# SerialKM.net
KiCad netlist of a schematic drawn in Altium Designer
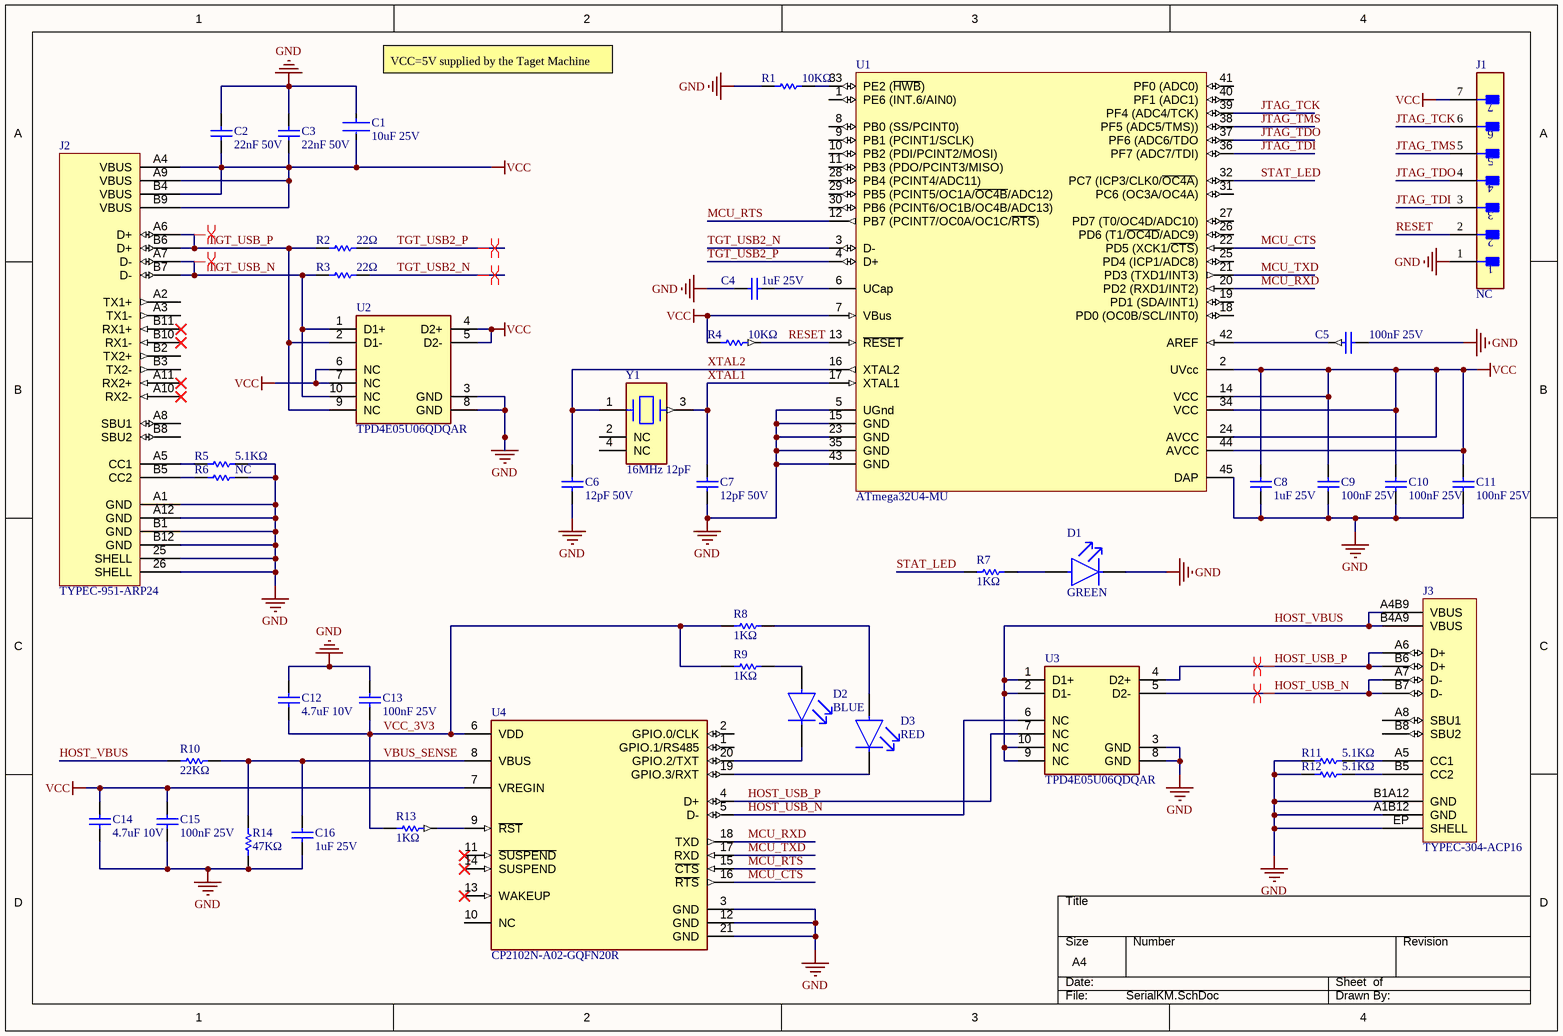
[diagram p0: SerialKM.SchDoc]

(export (version "E")
  (design (tool "Eeschema 10.0.6"))
  (components
    (comp (ref "C1")
      (value "10uF 25V")
      (footprint "FP-C1608-080-MFG")
      (description "CAP CER 10UF 25V X5R 0603")
      (fields (field (name "TOLERANCE") "20%"))
      (libsource (lib "Altium Content Vault") (part "11868f565c42a9108669ba33697ecf6"))
    )
    (comp (ref "C2")
      (value "22nF 50V")
      (footprint "CAPC1005X56X25LL10T15")
      (fields
        (field (name "PART NUMBER") "CM05X7R223K16AH.")
        (field (name "MANUFACTURER") "AVX Interconnect / Elco")
      )
      (libsource (lib "Altium Content Vault") (part "CAP"))
    )
    (comp (ref "C3")
      (value "22nF 50V")
      (footprint "CAPC1005X56X25LL10T15")
      (fields
        (field (name "PART NUMBER") "CM05X7R223K16AH.")
        (field (name "MANUFACTURER") "AVX Interconnect / Elco")
      )
      (libsource (lib "Altium Content Vault") (part "CAP"))
    )
    (comp (ref "C4")
      (value "1uF 25V")
      (footprint "CAPC1005X55X10LL05")
      (description "Chip Capacitor, 1 uF, +/- 10%, 16 V, -55 to 85 degC, 0402 (1005 Metric), RoHS, Tape and Reel")
      (fields
        (field (name "TOLERANCE") "±10%")
        (field (name "PCN PART NUMBER") "MLCCPartNumberChange30/Nov/2012")
      )
      (libsource (lib "Altium Content Vault") (part "CAP-NP-2"))
    )
    (comp (ref "C5")
      (value "100nF 25V")
      (footprint "CAPC1005X55X30LL05T10")
      (fields (field (name "MANUFACTURER") "Kemet") (field (name "PART NUMBER") "C0402C104K4RACTU"))
      (libsource (lib "") (part "CAP_1"))
    )
    (comp (ref "C6")
      (value "12pF 50V")
      (footprint "CAPC1005X61X26LL10T16")
      (fields (field (name "PART NUMBER") "VJ0402D120JXCAJ") (field (name "MANUFACTURER") "Vitramon"))
      (libsource (lib "Altium Content Vault") (part "CAP"))
    )
    (comp (ref "C7")
      (value "12pF 50V")
      (footprint "CAPC1005X61X26LL10T16")
      (fields (field (name "PART NUMBER") "VJ0402D120JXCAJ") (field (name "MANUFACTURER") "Vitramon"))
      (libsource (lib "Altium Content Vault") (part "CAP"))
    )
    (comp (ref "C8")
      (value "1uF 25V")
      (footprint "CAPC1005X55X10LL05")
      (description "Chip Capacitor, 1 uF, +/- 10%, 16 V, -55 to 85 degC, 0402 (1005 Metric), RoHS, Tape and Reel")
      (fields
        (field (name "TOLERANCE") "±10%")
        (field (name "PCN PART NUMBER") "MLCCPartNumberChange30/Nov/2012")
      )
      (libsource (lib "Altium Content Vault") (part "CAP-NP-2"))
    )
    (comp (ref "C9")
      (value "100nF 25V")
      (footprint "CAPC1005X55X30LL05T10")
      (fields (field (name "MANUFACTURER") "Kemet") (field (name "PART NUMBER") "C0402C104K4RACTU"))
      (libsource (lib "Altium Content Vault") (part "CAP"))
    )
    (comp (ref "C10")
      (value "100nF 25V")
      (footprint "CAPC1005X55X30LL05T10")
      (fields (field (name "MANUFACTURER") "Kemet") (field (name "PART NUMBER") "C0402C104K4RACTU"))
      (libsource (lib "Altium Content Vault") (part "CAP"))
    )
    (comp (ref "C11")
      (value "100nF 25V")
      (footprint "CAPC1005X55X30LL05T10")
      (fields (field (name "MANUFACTURER") "Kemet") (field (name "PART NUMBER") "C0402C104K4RACTU"))
      (libsource (lib "Altium Content Vault") (part "CAP"))
    )
    (comp (ref "C12")
      (value "4.7uF 10V")
      (footprint "CAPC1005X70X10LL20T00")
      (fields
        (field (name "MANUFACTURER") "AVX Interconnect / Elco")
        (field (name "PART NUMBER") "TACK475M003QTA")
      )
      (libsource (lib "Altium Content Vault") (part "CAP"))
    )
    (comp (ref "C13")
      (value "100nF 25V")
      (footprint "CAPC1005X55X30LL05T10")
      (fields (field (name "MANUFACTURER") "Kemet") (field (name "PART NUMBER") "C0402C104K4RACTU"))
      (libsource (lib "Altium Content Vault") (part "CAP"))
    )
    (comp (ref "C14")
      (value "4.7uF 10V")
      (footprint "CAPC1005X70X10LL20T00")
      (fields
        (field (name "MANUFACTURER") "AVX Interconnect / Elco")
        (field (name "PART NUMBER") "TACK475M003QTA")
      )
      (libsource (lib "Altium Content Vault") (part "CAP"))
    )
    (comp (ref "C15")
      (value "100nF 25V")
      (footprint "CAPC1005X55X30LL05T10")
      (fields (field (name "MANUFACTURER") "Kemet") (field (name "PART NUMBER") "C0402C104K4RACTU"))
      (libsource (lib "Altium Content Vault") (part "CAP"))
    )
    (comp (ref "C16")
      (value "1uF 25V")
      (footprint "CAPC1005X55X10LL05")
      (description "Chip Capacitor, 1 uF, +/- 10%, 16 V, -55 to 85 degC, 0402 (1005 Metric), RoHS, Tape and Reel")
      (fields
        (field (name "TOLERANCE") "±10%")
        (field (name "PCN PART NUMBER") "MLCCPartNumberChange30/Nov/2012")
      )
      (libsource (lib "Altium Content Vault") (part "CAP-NP-2"))
    )
    (comp (ref "D1")
      (value "GREEN")
      (footprint "FP-APHHS1005CGCK-MFG")
      (description "LED CLEAR CHIP SMD")
      (libsource (lib "Altium Content Vault") (part "8706943c75ba83719d021d2fdc84c58"))
    )
    (comp (ref "D2")
      (value "BLUE")
      (footprint "FP-APHHS1005CGCK-MFG")
      (description "LED CLEAR CHIP SMD")
      (libsource (lib "Altium Content Vault") (part "8706943c75ba83719d021d2fdc84c58"))
    )
    (comp (ref "D3")
      (value "RED")
      (footprint "FP-APHHS1005CGCK-MFG")
      (description "LED CLEAR CHIP SMD")
      (libsource (lib "Altium Content Vault") (part "8706943c75ba83719d021d2fdc84c58"))
    )
    (comp (ref "J1")
      (value "NC")
      (footprint "FP-GRPB071VWVN-RC-MFG")
      (description "Debug header")
      (libsource (lib "Altium Content Vault") (part "5bcee6b94e1fee4be3f4cc3a650a442"))
    )
    (comp (ref "J2")
      (value "TYPEC-951-ARP24")
      (footprint "TYPEC-951-ARP24")
      (description "Xunpu TYPEC-951-ARP24 USB Type-C Male Connector SMD")
      (libsource (lib "SerialKM") (part "TYPEC-951-ARP24"))
    )
    (comp (ref "J3")
      (value "TYPEC-304-ACP16")
      (footprint "TYPEC-304-ACP16")
      (description "Xunpu TYPEC-304-ACP16 USB Type-C  Socket 16P SMD")
      (libsource (lib "SerialKM") (part "TYPEC-304-ACP16"))
    )
    (comp (ref "R1")
      (value "10KΩ")
      (footprint "RESC1005X40X25LL05T10")
      (fields (field (name "PART NUMBER") "RC0402FR-075K1L") (field (name "MANUFACTURER") "Yageo / Phycomp"))
      (libsource (lib "Altium Content Vault") (part "RES"))
    )
    (comp (ref "R2")
      (value "22Ω")
      (footprint "RESC1005X40X25LL05T05")
      (fields (field (name "MANUFACTURER") "Vishay Dale") (field (name "PART NUMBER") "CRCW040222R0FKED"))
      (libsource (lib "Altium Content Vault") (part "RES"))
    )
    (comp (ref "R3")
      (value "22Ω")
      (footprint "RESC1005X40X25LL05T05")
      (fields (field (name "MANUFACTURER") "Vishay Dale") (field (name "PART NUMBER") "CRCW040222R0FKED"))
      (libsource (lib "Altium Content Vault") (part "RES"))
    )
    (comp (ref "R4")
      (value "10KΩ")
      (footprint "RESC1005X40X25LL05T10")
      (fields (field (name "PART NUMBER") "RC0402FR-075K1L") (field (name "MANUFACTURER") "Yageo / Phycomp"))
      (libsource (lib "") (part "RES_2"))
    )
    (comp (ref "R5")
      (value "5.1KΩ")
      (footprint "RESC1005X40X25LL05T10")
      (fields (field (name "PART NUMBER") "RC0402FR-075K1L") (field (name "MANUFACTURER") "Yageo / Phycomp"))
      (libsource (lib "Altium Content Vault") (part "RES"))
    )
    (comp (ref "R6")
      (value "NC")
      (footprint "RESC1005X40X25LL05T10")
      (fields (field (name "PART NUMBER") "RC0402FR-075K1L") (field (name "MANUFACTURER") "Yageo / Phycomp"))
      (libsource (lib "Altium Content Vault") (part "RES"))
    )
    (comp (ref "R7")
      (value "1KΩ")
      (footprint "RESC1005X40X25LL05T10")
      (fields (field (name "PART NUMBER") "RC0402FR-075K1L") (field (name "MANUFACTURER") "Yageo / Phycomp"))
      (libsource (lib "Altium Content Vault") (part "RES"))
    )
    (comp (ref "R8")
      (value "1KΩ")
      (footprint "RESC1005X40X25LL05T10")
      (fields (field (name "PART NUMBER") "RC0402FR-075K1L") (field (name "MANUFACTURER") "Yageo / Phycomp"))
      (libsource (lib "Altium Content Vault") (part "RES"))
    )
    (comp (ref "R9")
      (value "1KΩ")
      (footprint "RESC1005X40X25LL05T10")
      (fields (field (name "PART NUMBER") "RC0402FR-075K1L") (field (name "MANUFACTURER") "Yageo / Phycomp"))
      (libsource (lib "Altium Content Vault") (part "RES"))
    )
    (comp (ref "R10")
      (value "22KΩ")
      (footprint "RESC1005X40X25LL05T10")
      (fields (field (name "PART NUMBER") "RC0402FR-075K1L") (field (name "MANUFACTURER") "Yageo / Phycomp"))
      (libsource (lib "Altium Content Vault") (part "RES"))
    )
    (comp (ref "R11")
      (value "5.1KΩ")
      (footprint "RESC1005X40X25LL05T10")
      (fields (field (name "PART NUMBER") "RC0402FR-075K1L") (field (name "MANUFACTURER") "Yageo / Phycomp"))
      (libsource (lib "Altium Content Vault") (part "RES"))
    )
    (comp (ref "R12")
      (value "5.1KΩ")
      (footprint "RESC1005X40X25LL05T10")
      (fields (field (name "PART NUMBER") "RC0402FR-075K1L") (field (name "MANUFACTURER") "Yageo / Phycomp"))
      (libsource (lib "Altium Content Vault") (part "RES"))
    )
    (comp (ref "R13")
      (value "1KΩ")
      (footprint "RESC1005X40X25LL05T10")
      (fields (field (name "PART NUMBER") "RC0402FR-075K1L") (field (name "MANUFACTURER") "Yageo / Phycomp"))
      (libsource (lib "") (part "RES_1"))
    )
    (comp (ref "R14")
      (value "47KΩ")
      (footprint "RESC1005X40X25LL05T10")
      (fields (field (name "PART NUMBER") "RC0402FR-075K1L") (field (name "MANUFACTURER") "Yageo / Phycomp"))
      (libsource (lib "Altium Content Vault") (part "RES"))
    )
    (comp (ref "U1")
      (value "ATmega32U4-MU")
      (footprint "44PW_L")
      (libsource (lib "Altium Content Vault") (part "MC-8B-ATM16U4-SQ45"))
    )
    (comp (ref "U2")
      (value "TPD4E05U06QDQAR")
      (footprint "FP-DQA0010A-MFG")
      (description "TVS DIODE 5.5V 14V 10USON")
      (fields
        (field (name "MANUFACTURER PART NUMBER") "TPD4E05U06QDQARQ1")
        (field (name "OCTOPART") "https://octopart.com/tpd4e05u06qdqarq1-texas+instruments-48523459")
      )
      (libsource (lib "Altium Content Vault") (part "f11f7ff102fa2b028e1355c732c836d"))
    )
    (comp (ref "U3")
      (value "TPD4E05U06QDQAR")
      (footprint "FP-DQA0010A-MFG")
      (description "TVS DIODE 5.5V 14V 10USON")
      (fields
        (field (name "MANUFACTURER PART NUMBER") "TPD4E05U06QDQARQ1")
        (field (name "OCTOPART") "https://octopart.com/tpd4e05u06qdqarq1-texas+instruments-48523459")
      )
      (libsource (lib "Altium Content Vault") (part "f11f7ff102fa2b028e1355c732c836d"))
    )
    (comp (ref "U4")
      (value "CP2102N-A02-GQFN20R")
      (footprint "FP-CP2102N-A02-GQFN20R-MFG")
      (description "IC USB TO UART BRIDGE QFN20")
      (libsource (lib "Altium Content Vault") (part "12297b18919ed2bc2a0fed00377f037"))
    )
    (comp (ref "Y1")
      (value "16MHz 12pF")
      (footprint "FP-XRCGB-MFG")
      (description "CRYSTAL 16.0000MHZ")
      (fields (field (name "TOLERANCE") "20ppm"))
      (libsource (lib "Altium Content Vault") (part "069643b213014e47d16623c4b5cd2db"))
    )
  )
  (nets
    (net (code "1") (name "/HOST_USB_N") (class "Default")
      (node (ref "J3") (pin "A7") (pinfunction "D-_A7") (pintype "bidirectional"))
      (node (ref "J3") (pin "B7") (pinfunction "D-_B7") (pintype "bidirectional"))
      (node (ref "U3") (pin "5") (pinfunction "D2-_5") (pintype "passive"))
      (node (ref "U3") (pin "6") (pinfunction "NC_6") (pintype "passive"))
      (node (ref "U4") (pin "5") (pinfunction "D-_5") (pintype "bidirectional"))
    )
    (net (code "2") (name "/HOST_USB_P") (class "Default")
      (node (ref "J3") (pin "A6") (pinfunction "D+_A6") (pintype "bidirectional"))
      (node (ref "J3") (pin "B6") (pinfunction "D+_B6") (pintype "bidirectional"))
      (node (ref "U3") (pin "4") (pinfunction "D2+_4") (pintype "passive"))
      (node (ref "U3") (pin "7") (pinfunction "NC_7") (pintype "passive"))
      (node (ref "U4") (pin "4") (pinfunction "D+_4") (pintype "bidirectional"))
    )
    (net (code "3") (name "/HOST_VBUS") (class "Default")
      (node (ref "J3") (pin "A4B9") (pinfunction "VBUS_A4B9") (pintype "passive"))
      (node (ref "J3") (pin "B4A9") (pinfunction "VBUS_B4A9") (pintype "passive"))
      (node (ref "R10") (pin "1") (pinfunction "1_1") (pintype "passive"))
      (node (ref "U3") (pin "1") (pinfunction "D1+_1") (pintype "passive"))
      (node (ref "U3") (pin "10") (pinfunction "NC_10") (pintype "passive"))
      (node (ref "U3") (pin "2") (pinfunction "D1-_2") (pintype "passive"))
      (node (ref "U3") (pin "9") (pinfunction "NC_9") (pintype "passive"))
    )
    (net (code "4") (name "/JTAG_TCK") (class "Default")
      (node (ref "J1") (pin "6") (pinfunction "6_6") (pintype "passive"))
      (node (ref "U1") (pin "39") (pinfunction "PF4_(ADC4/TCK)_39") (pintype "bidirectional"))
    )
    (net (code "5") (name "/JTAG_TDI") (class "Default")
      (node (ref "J1") (pin "3") (pinfunction "3_3") (pintype "passive"))
      (node (ref "U1") (pin "36") (pinfunction "PF7_(ADC7/TDI)_36") (pintype "bidirectional"))
    )
    (net (code "6") (name "/JTAG_TDO") (class "Default")
      (node (ref "J1") (pin "4") (pinfunction "4_4") (pintype "passive"))
      (node (ref "U1") (pin "37") (pinfunction "PF6_(ADC6/TDO_37") (pintype "bidirectional"))
    )
    (net (code "7") (name "/JTAG_TMS") (class "Default")
      (node (ref "J1") (pin "5") (pinfunction "5_5") (pintype "passive"))
      (node (ref "U1") (pin "38") (pinfunction "PF5_(ADC5/TMS))_38") (pintype "bidirectional"))
    )
    (net (code "8") (name "/MCU_CTS") (class "Default")
      (node (ref "U1") (pin "22") (pinfunction "PD5_(XCK1/~{CTS})_22") (pintype "input"))
      (node (ref "U4") (pin "16") (pinfunction "~{RTS}_16") (pintype "output"))
    )
    (net (code "9") (name "/MCU_RTS") (class "Default")
      (node (ref "U1") (pin "12") (pinfunction "PB7_(PCINT7/OC0A/OC1C/~{RTS})_12") (pintype "output"))
      (node (ref "U4") (pin "15") (pinfunction "~{CTS}_15") (pintype "input"))
    )
    (net (code "10") (name "/MCU_RXD") (class "Default")
      (node (ref "U1") (pin "20") (pinfunction "PD2_(RXD1/INT2)_20") (pintype "input"))
      (node (ref "U4") (pin "18") (pinfunction "TXD_18") (pintype "output"))
    )
    (net (code "11") (name "/MCU_TXD") (class "Default")
      (node (ref "U1") (pin "21") (pinfunction "PD3_(TXD1/INT3)_21") (pintype "output"))
      (node (ref "U4") (pin "17") (pinfunction "RXD_17") (pintype "input"))
    )
    (net (code "12") (name "/RESET") (class "Default")
      (node (ref "J1") (pin "2") (pinfunction "2_2") (pintype "passive"))
      (node (ref "R4") (pin "1") (pinfunction "1_1") (pintype "output"))
      (node (ref "U1") (pin "13") (pinfunction "~{RESET}_13") (pintype "input"))
    )
    (net (code "13") (name "/STAT_LED") (class "Default")
      (node (ref "R7") (pin "1") (pinfunction "1_1") (pintype "passive"))
      (node (ref "U1") (pin "32") (pinfunction "PC7_(ICP3/CLK0/~{OC4A})_32") (pintype "bidirectional"))
    )
    (net (code "14") (name "/TGT_USB2_N") (class "Default")
      (node (ref "R3") (pin "2") (pinfunction "2_2") (pintype "passive"))
      (node (ref "U1") (pin "3") (pinfunction "D-_3") (pintype "bidirectional"))
    )
    (net (code "15") (name "/TGT_USB2_P") (class "Default")
      (node (ref "R2") (pin "2") (pinfunction "2_2") (pintype "passive"))
      (node (ref "U1") (pin "4") (pinfunction "D+_4") (pintype "bidirectional"))
    )
    (net (code "16") (name "/TGT_USB_N") (class "Default")
      (node (ref "J2") (pin "A7") (pinfunction "D-_A7") (pintype "bidirectional"))
      (node (ref "J2") (pin "B7") (pinfunction "D-_B7") (pintype "bidirectional"))
      (node (ref "R3") (pin "1") (pinfunction "1_1") (pintype "passive"))
      (node (ref "U2") (pin "1") (pinfunction "D1+_1") (pintype "passive"))
      (node (ref "U2") (pin "10") (pinfunction "NC_10") (pintype "passive"))
    )
    (net (code "17") (name "/TGT_USB_P") (class "Default")
      (node (ref "J2") (pin "A6") (pinfunction "D+_A6") (pintype "bidirectional"))
      (node (ref "J2") (pin "B6") (pinfunction "D+_B6") (pintype "bidirectional"))
      (node (ref "R2") (pin "1") (pinfunction "1_1") (pintype "passive"))
      (node (ref "U2") (pin "2") (pinfunction "D1-_2") (pintype "passive"))
      (node (ref "U2") (pin "9") (pinfunction "NC_9") (pintype "passive"))
    )
    (net (code "18") (name "/VBUS_SENSE") (class "Default")
      (node (ref "C16") (pin "2") (pinfunction "2_2") (pintype "passive"))
      (node (ref "R10") (pin "2") (pinfunction "2_2") (pintype "passive"))
      (node (ref "R14") (pin "2") (pinfunction "2_2") (pintype "passive"))
      (node (ref "U4") (pin "8") (pinfunction "VBUS_8") (pintype "power_in"))
    )
    (net (code "19") (name "/VCC_3V3") (class "Default")
      (node (ref "C12") (pin "1") (pinfunction "1_1") (pintype "passive"))
      (node (ref "C13") (pin "1") (pinfunction "1_1") (pintype "passive"))
      (node (ref "R13") (pin "1") (pinfunction "1_1") (pintype "passive"))
      (node (ref "R8") (pin "1") (pinfunction "1_1") (pintype "passive"))
      (node (ref "R9") (pin "2") (pinfunction "2_2") (pintype "passive"))
      (node (ref "U4") (pin "6") (pinfunction "VDD_6") (pintype "power_in"))
    )
    (net (code "20") (name "/XTAL1") (class "Default")
      (node (ref "C7") (pin "2") (pinfunction "2_2") (pintype "passive"))
      (node (ref "U1") (pin "17") (pinfunction "XTAL1_17") (pintype "input"))
      (node (ref "Y1") (pin "3") (pinfunction "2_Crystal_terminal_3") (pintype "output"))
    )
    (net (code "21") (name "/XTAL2") (class "Default")
      (node (ref "C6") (pin "2") (pinfunction "2_2") (pintype "passive"))
      (node (ref "U1") (pin "16") (pinfunction "XTAL2_16") (pintype "output"))
      (node (ref "Y1") (pin "1") (pinfunction "1_Crystal_terminal_1") (pintype "passive"))
    )
    (net (code "22") (name "GND") (class "Default")
      (node (ref "C1") (pin "1") (pinfunction "1_1") (pintype "passive"))
      (node (ref "C10") (pin "1") (pinfunction "1_1") (pintype "passive"))
      (node (ref "C11") (pin "1") (pinfunction "1_1") (pintype "passive"))
      (node (ref "C12") (pin "2") (pinfunction "2_2") (pintype "passive"))
      (node (ref "C13") (pin "2") (pinfunction "2_2") (pintype "passive"))
      (node (ref "C14") (pin "1") (pinfunction "1_1") (pintype "passive"))
      (node (ref "C15") (pin "1") (pinfunction "1_1") (pintype "passive"))
      (node (ref "C16") (pin "1") (pinfunction "1_1") (pintype "passive"))
      (node (ref "C2") (pin "2") (pinfunction "2_2") (pintype "passive"))
      (node (ref "C3") (pin "2") (pinfunction "2_2") (pintype "passive"))
      (node (ref "C4") (pin "1") (pinfunction "1_1") (pintype "passive"))
      (node (ref "C5") (pin "1") (pinfunction "1_1") (pintype "passive"))
      (node (ref "C6") (pin "1") (pinfunction "1_1") (pintype "passive"))
      (node (ref "C7") (pin "1") (pinfunction "1_1") (pintype "passive"))
      (node (ref "C8") (pin "2") (pinfunction "2_2") (pintype "passive"))
      (node (ref "C9") (pin "1") (pinfunction "1_1") (pintype "passive"))
      (node (ref "D1") (pin "1") (pinfunction "C_1") (pintype "passive"))
      (node (ref "J1") (pin "1") (pinfunction "1_1") (pintype "passive"))
      (node (ref "J2") (pin "25") (pinfunction "SHELL_25") (pintype "passive"))
      (node (ref "J2") (pin "26") (pinfunction "SHELL_26") (pintype "passive"))
      (node (ref "J2") (pin "A1") (pinfunction "GND_A1") (pintype "passive"))
      (node (ref "J2") (pin "A12") (pinfunction "GND_A12") (pintype "passive"))
      (node (ref "J2") (pin "B1") (pinfunction "GND_B1") (pintype "passive"))
      (node (ref "J2") (pin "B12") (pinfunction "GND_B12") (pintype "passive"))
      (node (ref "J3") (pin "A1B12") (pinfunction "GND_A1B12") (pintype "passive"))
      (node (ref "J3") (pin "B1A12") (pinfunction "GND_B1A12") (pintype "passive"))
      (node (ref "J3") (pin "EP") (pinfunction "SHELL_EP") (pintype "passive"))
      (node (ref "R1") (pin "2") (pinfunction "2_2") (pintype "passive"))
      (node (ref "R11") (pin "1") (pinfunction "1_1") (pintype "passive"))
      (node (ref "R12") (pin "1") (pinfunction "1_1") (pintype "passive"))
      (node (ref "R14") (pin "1") (pinfunction "1_1") (pintype "passive"))
      (node (ref "R5") (pin "2") (pinfunction "2_2") (pintype "passive"))
      (node (ref "R6") (pin "2") (pinfunction "2_2") (pintype "passive"))
      (node (ref "U1") (pin "15") (pinfunction "GND_15") (pintype "power_in"))
      (node (ref "U1") (pin "23") (pinfunction "GND_23") (pintype "power_in"))
      (node (ref "U1") (pin "35") (pinfunction "GND_35") (pintype "power_in"))
      (node (ref "U1") (pin "43") (pinfunction "GND_43") (pintype "power_in"))
      (node (ref "U1") (pin "45") (pinfunction "DAP_45") (pintype "power_in"))
      (node (ref "U1") (pin "5") (pinfunction "UGnd_5") (pintype "power_in"))
      (node (ref "U2") (pin "3") (pinfunction "GND_3") (pintype "power_in"))
      (node (ref "U2") (pin "8") (pinfunction "GND_8") (pintype "power_in"))
      (node (ref "U3") (pin "3") (pinfunction "GND_3") (pintype "power_in"))
      (node (ref "U3") (pin "8") (pinfunction "GND_8") (pintype "power_in"))
      (node (ref "U4") (pin "12") (pinfunction "GND_12") (pintype "power_in"))
      (node (ref "U4") (pin "21") (pinfunction "GND_21") (pintype "power_in"))
      (node (ref "U4") (pin "3") (pinfunction "GND_3") (pintype "power_in"))
    )
    (net (code "23") (name "Net-(D1-A)") (class "Default")
      (node (ref "D1") (pin "2") (pinfunction "A_2") (pintype "passive"))
      (node (ref "R7") (pin "2") (pinfunction "2_2") (pintype "passive"))
    )
    (net (code "24") (name "Net-(D2-A)") (class "Default")
      (node (ref "D2") (pin "2") (pinfunction "A_2") (pintype "passive"))
      (node (ref "R9") (pin "1") (pinfunction "1_1") (pintype "passive"))
    )
    (net (code "25") (name "Net-(D2-C)") (class "Default")
      (node (ref "D2") (pin "1") (pinfunction "C_1") (pintype "passive"))
      (node (ref "U4") (pin "20") (pinfunction "GPIO.2/TXT_20") (pintype "bidirectional"))
    )
    (net (code "26") (name "Net-(D3-A)") (class "Default")
      (node (ref "D3") (pin "2") (pinfunction "A_2") (pintype "passive"))
      (node (ref "R8") (pin "2") (pinfunction "2_2") (pintype "passive"))
    )
    (net (code "27") (name "Net-(D3-C)") (class "Default")
      (node (ref "D3") (pin "1") (pinfunction "C_1") (pintype "passive"))
      (node (ref "U4") (pin "19") (pinfunction "GPIO.3/RXT_19") (pintype "bidirectional"))
    )
    (net (code "28") (name "Net-(J2-CC1)") (class "Default")
      (node (ref "J2") (pin "A5") (pinfunction "CC1_A5") (pintype "passive"))
      (node (ref "R5") (pin "1") (pinfunction "1_1") (pintype "passive"))
    )
    (net (code "29") (name "Net-(J2-CC2)") (class "Default")
      (node (ref "J2") (pin "B5") (pinfunction "CC2_B5") (pintype "passive"))
      (node (ref "R6") (pin "1") (pinfunction "1_1") (pintype "passive"))
    )
    (net (code "30") (name "Net-(J3-CC1)") (class "Default")
      (node (ref "J3") (pin "A5") (pinfunction "CC1_A5") (pintype "passive"))
      (node (ref "R11") (pin "2") (pinfunction "2_2") (pintype "passive"))
    )
    (net (code "31") (name "Net-(J3-CC2)") (class "Default")
      (node (ref "J3") (pin "B5") (pinfunction "CC2_B5") (pintype "passive"))
      (node (ref "R12") (pin "2") (pinfunction "2_2") (pintype "passive"))
    )
    (net (code "32") (name "Net-(U1-AREF)") (class "Default")
      (node (ref "C5") (pin "2") (pinfunction "2_2") (pintype "output"))
      (node (ref "U1") (pin "42") (pinfunction "AREF_42") (pintype "input"))
    )
    (net (code "33") (name "Net-(U1-PE2_(~{HWB}))") (class "Default")
      (node (ref "R1") (pin "1") (pinfunction "1_1") (pintype "passive"))
      (node (ref "U1") (pin "33") (pinfunction "PE2_(~{HWB})_33") (pintype "bidirectional"))
    )
    (net (code "34") (name "Net-(U1-UCap)") (class "Default")
      (node (ref "C4") (pin "2") (pinfunction "2_2") (pintype "passive"))
      (node (ref "U1") (pin "6") (pinfunction "UCap_6") (pintype "passive"))
    )
    (net (code "35") (name "Net-(U4-~{RST})") (class "Default")
      (node (ref "R13") (pin "2") (pinfunction "2_2") (pintype "output"))
      (node (ref "U4") (pin "9") (pinfunction "~{RST}_9") (pintype "input"))
    )
    (net (code "36") (name "VCC") (class "Default")
      (node (ref "C1") (pin "2") (pinfunction "2_2") (pintype "passive"))
      (node (ref "C10") (pin "2") (pinfunction "2_2") (pintype "passive"))
      (node (ref "C11") (pin "2") (pinfunction "2_2") (pintype "passive"))
      (node (ref "C14") (pin "2") (pinfunction "2_2") (pintype "passive"))
      (node (ref "C15") (pin "2") (pinfunction "2_2") (pintype "passive"))
      (node (ref "C2") (pin "1") (pinfunction "1_1") (pintype "passive"))
      (node (ref "C3") (pin "1") (pinfunction "1_1") (pintype "passive"))
      (node (ref "C8") (pin "1") (pinfunction "1_1") (pintype "passive"))
      (node (ref "C9") (pin "2") (pinfunction "2_2") (pintype "passive"))
      (node (ref "J1") (pin "7") (pinfunction "7_7") (pintype "passive"))
      (node (ref "J2") (pin "A4") (pinfunction "VBUS_A4") (pintype "power_in"))
      (node (ref "J2") (pin "A9") (pinfunction "VBUS_A9") (pintype "power_in"))
      (node (ref "J2") (pin "B4") (pinfunction "VBUS_B4") (pintype "power_in"))
      (node (ref "J2") (pin "B9") (pinfunction "VBUS_B9") (pintype "power_in"))
      (node (ref "R4") (pin "2") (pinfunction "2_2") (pintype "passive"))
      (node (ref "U1") (pin "14") (pinfunction "VCC_14") (pintype "power_in"))
      (node (ref "U1") (pin "2") (pinfunction "UVcc_2") (pintype "power_in"))
      (node (ref "U1") (pin "24") (pinfunction "AVCC_24") (pintype "power_in"))
      (node (ref "U1") (pin "34") (pinfunction "VCC_34") (pintype "power_in"))
      (node (ref "U1") (pin "44") (pinfunction "AVCC_44") (pintype "power_in"))
      (node (ref "U1") (pin "7") (pinfunction "VBus_7") (pintype "input"))
      (node (ref "U2") (pin "4") (pinfunction "D2+_4") (pintype "passive"))
      (node (ref "U2") (pin "5") (pinfunction "D2-_5") (pintype "passive"))
      (node (ref "U2") (pin "6") (pinfunction "NC_6") (pintype "passive"))
      (node (ref "U2") (pin "7") (pinfunction "NC_7") (pintype "passive"))
      (node (ref "U4") (pin "7") (pinfunction "VREGIN_7") (pintype "passive"))
    )
    (net (code "37") (name "unconnected-(J2-RX1+-PadB11)") (class "Default")
      (node (ref "J2") (pin "B11") (pinfunction "RX1+_B11") (pintype "input+no_connect"))
    )
    (net (code "38") (name "unconnected-(J2-RX1--PadB10)") (class "Default")
      (node (ref "J2") (pin "B10") (pinfunction "RX1-_B10") (pintype "input+no_connect"))
    )
    (net (code "39") (name "unconnected-(J2-RX2+-PadA11)") (class "Default")
      (node (ref "J2") (pin "A11") (pinfunction "RX2+_A11") (pintype "input+no_connect"))
    )
    (net (code "40") (name "unconnected-(J2-RX2--PadA10)") (class "Default")
      (node (ref "J2") (pin "A10") (pinfunction "RX2-_A10") (pintype "input+no_connect"))
    )
    (net (code "41") (name "unconnected-(J2-SBU1-PadA8)") (class "Default")
      (node (ref "J2") (pin "A8") (pinfunction "SBU1_A8") (pintype "bidirectional"))
    )
    (net (code "42") (name "unconnected-(J2-SBU2-PadB8)") (class "Default")
      (node (ref "J2") (pin "B8") (pinfunction "SBU2_B8") (pintype "bidirectional"))
    )
    (net (code "43") (name "unconnected-(J2-TX1+-PadA2)") (class "Default")
      (node (ref "J2") (pin "A2") (pinfunction "TX1+_A2") (pintype "output"))
    )
    (net (code "44") (name "unconnected-(J2-TX1--PadA3)") (class "Default")
      (node (ref "J2") (pin "A3") (pinfunction "TX1-_A3") (pintype "output"))
    )
    (net (code "45") (name "unconnected-(J2-TX2+-PadB2)") (class "Default")
      (node (ref "J2") (pin "B2") (pinfunction "TX2+_B2") (pintype "output"))
    )
    (net (code "46") (name "unconnected-(J2-TX2--PadB3)") (class "Default")
      (node (ref "J2") (pin "B3") (pinfunction "TX2-_B3") (pintype "output"))
    )
    (net (code "47") (name "unconnected-(J3-SBU1-PadA8)") (class "Default")
      (node (ref "J3") (pin "A8") (pinfunction "SBU1_A8") (pintype "bidirectional"))
    )
    (net (code "48") (name "unconnected-(J3-SBU2-PadB8)") (class "Default")
      (node (ref "J3") (pin "B8") (pinfunction "SBU2_B8") (pintype "bidirectional"))
    )
    (net (code "49") (name "unconnected-(U1-PB0_(SS{slash}PCINT0)-Pad8)") (class "Default")
      (node (ref "U1") (pin "8") (pinfunction "PB0_(SS/PCINT0)_8") (pintype "bidirectional"))
    )
    (net (code "50") (name "unconnected-(U1-PB1_(PCINT1{slash}SCLK)-Pad9)") (class "Default")
      (node (ref "U1") (pin "9") (pinfunction "PB1_(PCINT1/SCLK)_9") (pintype "bidirectional"))
    )
    (net (code "51") (name "unconnected-(U1-PB2_(PDI{slash}PCINT2{slash}MOSI)-Pad10)") (class "Default")
      (node (ref "U1") (pin "10") (pinfunction "PB2_(PDI/PCINT2/MOSI)_10") (pintype "bidirectional"))
    )
    (net (code "52") (name "unconnected-(U1-PB3_(PDO{slash}PCINT3{slash}MISO)-Pad11)") (class "Default")
      (node (ref "U1") (pin "11") (pinfunction "PB3_(PDO/PCINT3/MISO)_11") (pintype "bidirectional"))
    )
    (net (code "53") (name "unconnected-(U1-PB4_(PCINT4{slash}ADC11)-Pad28)") (class "Default")
      (node (ref "U1") (pin "28") (pinfunction "PB4_(PCINT4/ADC11)_28") (pintype "bidirectional"))
    )
    (net (code "54") (name "unconnected-(U1-PB5_(PCINT5{slash}OC1A{slash}~{OC4B}{slash}ADC12)-Pad29)") (class "Default")
      (node (ref "U1") (pin "29") (pinfunction "PB5_(PCINT5/OC1A/~{OC4B}/ADC12)_29") (pintype "bidirectional"))
    )
    (net (code "55") (name "unconnected-(U1-PB6_(PCINT6{slash}OC1B{slash}OC4B{slash}ADC13)-Pad30)") (class "Default")
      (node (ref "U1") (pin "30") (pinfunction "PB6_(PCINT6/OC1B/OC4B/ADC13)_30") (pintype "bidirectional"))
    )
    (net (code "56") (name "unconnected-(U1-PC6_(OC3A{slash}OC4A)-Pad31)") (class "Default")
      (node (ref "U1") (pin "31") (pinfunction "PC6_(OC3A/OC4A)_31") (pintype "bidirectional"))
    )
    (net (code "57") (name "unconnected-(U1-PD0_(OC0B{slash}SCL{slash}INT0)-Pad18)") (class "Default")
      (node (ref "U1") (pin "18") (pinfunction "PD0_(OC0B/SCL/INT0)_18") (pintype "bidirectional"))
    )
    (net (code "58") (name "unconnected-(U1-PD1_(SDA{slash}INT1)-Pad19)") (class "Default")
      (node (ref "U1") (pin "19") (pinfunction "PD1_(SDA/INT1)_19") (pintype "bidirectional"))
    )
    (net (code "59") (name "unconnected-(U1-PD4_(ICP1{slash}ADC8)-Pad25)") (class "Default")
      (node (ref "U1") (pin "25") (pinfunction "PD4_(ICP1/ADC8)_25") (pintype "bidirectional"))
    )
    (net (code "60") (name "unconnected-(U1-PD6_(T1{slash}~{OC4D}{slash}ADC9)-Pad26)") (class "Default")
      (node (ref "U1") (pin "26") (pinfunction "PD6_(T1/~{OC4D}/ADC9)_26") (pintype "bidirectional"))
    )
    (net (code "61") (name "unconnected-(U1-PD7_(T0{slash}OC4D{slash}ADC10)-Pad27)") (class "Default")
      (node (ref "U1") (pin "27") (pinfunction "PD7_(T0/OC4D/ADC10)_27") (pintype "bidirectional"))
    )
    (net (code "62") (name "unconnected-(U1-PE6_(INT.6{slash}AIN0)-Pad1)") (class "Default")
      (node (ref "U1") (pin "1") (pinfunction "PE6_(INT.6/AIN0)_1") (pintype "bidirectional"))
    )
    (net (code "63") (name "unconnected-(U1-PF0_(ADC0)-Pad41)") (class "Default")
      (node (ref "U1") (pin "41") (pinfunction "PF0_(ADC0)_41") (pintype "bidirectional"))
    )
    (net (code "64") (name "unconnected-(U1-PF1_(ADC1)-Pad40)") (class "Default")
      (node (ref "U1") (pin "40") (pinfunction "PF1_(ADC1)_40") (pintype "bidirectional"))
    )
    (net (code "65") (name "unconnected-(U4-GPIO.0{slash}CLK-Pad2)") (class "Default")
      (node (ref "U4") (pin "2") (pinfunction "GPIO.0/CLK_2") (pintype "bidirectional"))
    )
    (net (code "66") (name "unconnected-(U4-GPIO.1{slash}RS485-Pad1)") (class "Default")
      (node (ref "U4") (pin "1") (pinfunction "GPIO.1/RS485_1") (pintype "bidirectional"))
    )
    (net (code "67") (name "unconnected-(U4-NC-Pad10)") (class "Default")
      (node (ref "U4") (pin "10") (pinfunction "NC_10") (pintype "passive"))
    )
    (net (code "68") (name "unconnected-(U4-SUSPEND-Pad14)") (class "Default")
      (node (ref "U4") (pin "14") (pinfunction "SUSPEND_14") (pintype "input+no_connect"))
    )
    (net (code "69") (name "unconnected-(U4-WAKEUP-Pad13)") (class "Default")
      (node (ref "U4") (pin "13") (pinfunction "WAKEUP_13") (pintype "input+no_connect"))
    )
    (net (code "70") (name "unconnected-(U4-~{SUSPEND}-Pad11)") (class "Default")
      (node (ref "U4") (pin "11") (pinfunction "~{SUSPEND}_11") (pintype "input+no_connect"))
    )
    (net (code "71") (name "unconnected-(Y1-NC-Pad2)") (class "Default")
      (node (ref "Y1") (pin "2") (pinfunction "NC_2") (pintype "passive"))
    )
    (net (code "72") (name "unconnected-(Y1-NC-Pad4)") (class "Default")
      (node (ref "Y1") (pin "4") (pinfunction "NC_4") (pintype "passive"))
    )
  )
)
